# LED_current_source.net
KiCad netlist of a schematic drawn in EAGLE
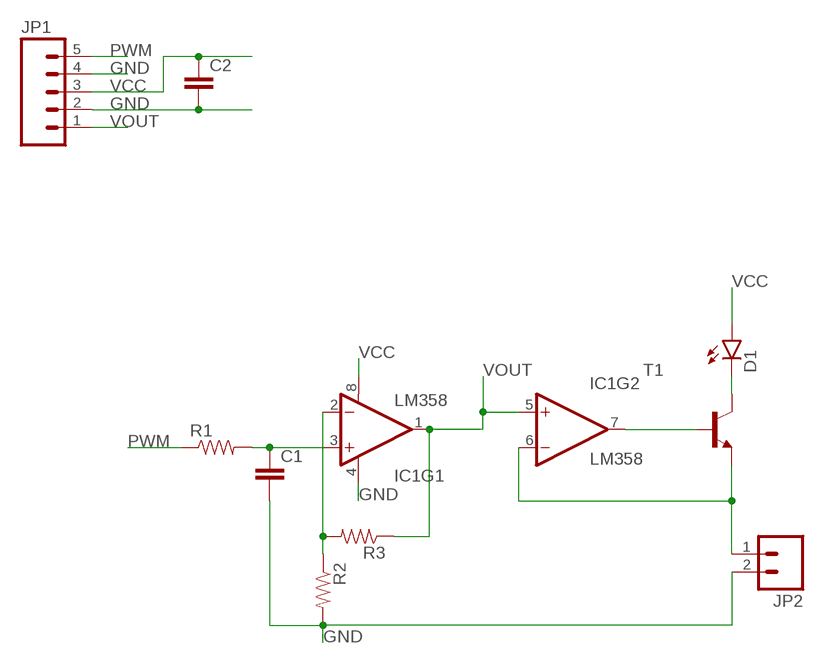
[diagram p0: schematic, sheet 1]

(export (version "E")
  (design (tool "Eeschema 10.0.6"))
  (components
    (comp (ref "C1")
      (value "CAP0603-CAP")
      (footprint "eagle-import:0603-CAP")
      (libsource (lib "eagle-import") (part "CAP0603-CAP"))
    )
    (comp (ref "C2")
      (value "CAP0603-CAP")
      (footprint "eagle-import:0603-CAP")
      (libsource (lib "eagle-import") (part "CAP0603-CAP"))
    )
    (comp (ref "D1")
      (value "LED5MM")
      (footprint "eagle-import:LED5MM")
      (libsource (lib "eagle-import") (part "LED5MM"))
    )
    (comp (ref "IC1")
      (value "LM358")
      (footprint "eagle-import:DIP08")
      (libsource (lib "eagle-import") (part "LM358"))
    )
    (comp (ref "JP1")
      (value "M05PTH")
      (footprint "eagle-import:1X05")
      (libsource (lib "eagle-import") (part "M05PTH"))
    )
    (comp (ref "JP2")
      (value "M02PTH")
      (footprint "eagle-import:1X02")
      (libsource (lib "eagle-import") (part "M02PTH"))
    )
    (comp (ref "R1")
      (value "RESISTOR0603-RES")
      (footprint "eagle-import:0603-RES")
      (libsource (lib "eagle-import") (part "RESISTOR0603-RES"))
    )
    (comp (ref "R2")
      (value "RESISTOR0603-RES")
      (footprint "eagle-import:0603-RES")
      (libsource (lib "eagle-import") (part "RESISTOR0603-RES"))
    )
    (comp (ref "R3")
      (value "RESISTOR0603-RES")
      (footprint "eagle-import:0603-RES")
      (libsource (lib "eagle-import") (part "RESISTOR0603-RES"))
    )
    (comp (ref "T1")
      (value "2N2222-NPN-TO92-EBC")
      (footprint "eagle-import:TO92-EBC")
      (libsource (lib "eagle-import") (part "-NPN-TO92-EBC2N2222"))
    )
  )
  (nets
    (net (code "1") (name "/GND") (class "Default")
      (node (ref "C1") (pin "2") (pinfunction "2_2") (pintype "passive"))
      (node (ref "C2") (pin "2") (pinfunction "2_2") (pintype "passive"))
      (node (ref "IC1") (pin "4") (pinfunction "V-_4") (pintype "power_in"))
      (node (ref "JP1") (pin "2") (pinfunction "2_2") (pintype "passive"))
      (node (ref "JP1") (pin "4") (pinfunction "4_4") (pintype "passive"))
      (node (ref "JP2") (pin "2") (pinfunction "2_2") (pintype "passive"))
      (node (ref "R2") (pin "2") (pinfunction "2_2") (pintype "passive"))
    )
    (net (code "2") (name "/PWM") (class "Default")
      (node (ref "JP1") (pin "5") (pinfunction "5_5") (pintype "passive"))
      (node (ref "R1") (pin "1") (pinfunction "1_1") (pintype "passive"))
    )
    (net (code "3") (name "/VCC") (class "Default")
      (node (ref "C2") (pin "1") (pinfunction "1_1") (pintype "passive"))
      (node (ref "D1") (pin "A") (pinfunction "A_A") (pintype "passive"))
      (node (ref "IC1") (pin "8") (pinfunction "V+_8") (pintype "power_in"))
      (node (ref "JP1") (pin "3") (pinfunction "3_3") (pintype "passive"))
    )
    (net (code "4") (name "/VOUT") (class "Default")
      (node (ref "IC1") (pin "1") (pinfunction "OUT_1") (pintype "output"))
      (node (ref "IC1") (pin "5") (pinfunction "+IN_5") (pintype "input"))
      (node (ref "JP1") (pin "1") (pinfunction "1_1") (pintype "passive"))
      (node (ref "R3") (pin "1") (pinfunction "1_1") (pintype "passive"))
    )
    (net (code "5") (name "Net-(D1-C)") (class "Default")
      (node (ref "D1") (pin "K") (pinfunction "C_K") (pintype "passive"))
      (node (ref "T1") (pin "C") (pinfunction "C_C") (pintype "passive"))
    )
    (net (code "6") (name "Net-(IC1A-+IN)") (class "Default")
      (node (ref "C1") (pin "1") (pinfunction "1_1") (pintype "passive"))
      (node (ref "IC1") (pin "3") (pinfunction "+IN_3") (pintype "input"))
      (node (ref "R1") (pin "2") (pinfunction "2_2") (pintype "passive"))
    )
    (net (code "7") (name "Net-(IC1A--IN)") (class "Default")
      (node (ref "IC1") (pin "2") (pinfunction "-IN_2") (pintype "input"))
      (node (ref "R2") (pin "1") (pinfunction "1_1") (pintype "passive"))
      (node (ref "R3") (pin "2") (pinfunction "2_2") (pintype "passive"))
    )
    (net (code "8") (name "Net-(IC1B--IN)") (class "Default")
      (node (ref "IC1") (pin "6") (pinfunction "-IN_6") (pintype "input"))
      (node (ref "JP2") (pin "1") (pinfunction "1_1") (pintype "passive"))
      (node (ref "T1") (pin "E") (pinfunction "E_E") (pintype "passive"))
    )
    (net (code "9") (name "Net-(IC1B-OUT)") (class "Default")
      (node (ref "IC1") (pin "7") (pinfunction "OUT_7") (pintype "output"))
      (node (ref "T1") (pin "B") (pinfunction "B_B") (pintype "passive"))
    )
  )
)
